# microcontroller.net
KiCad netlist of a schematic drawn in Altium Designer
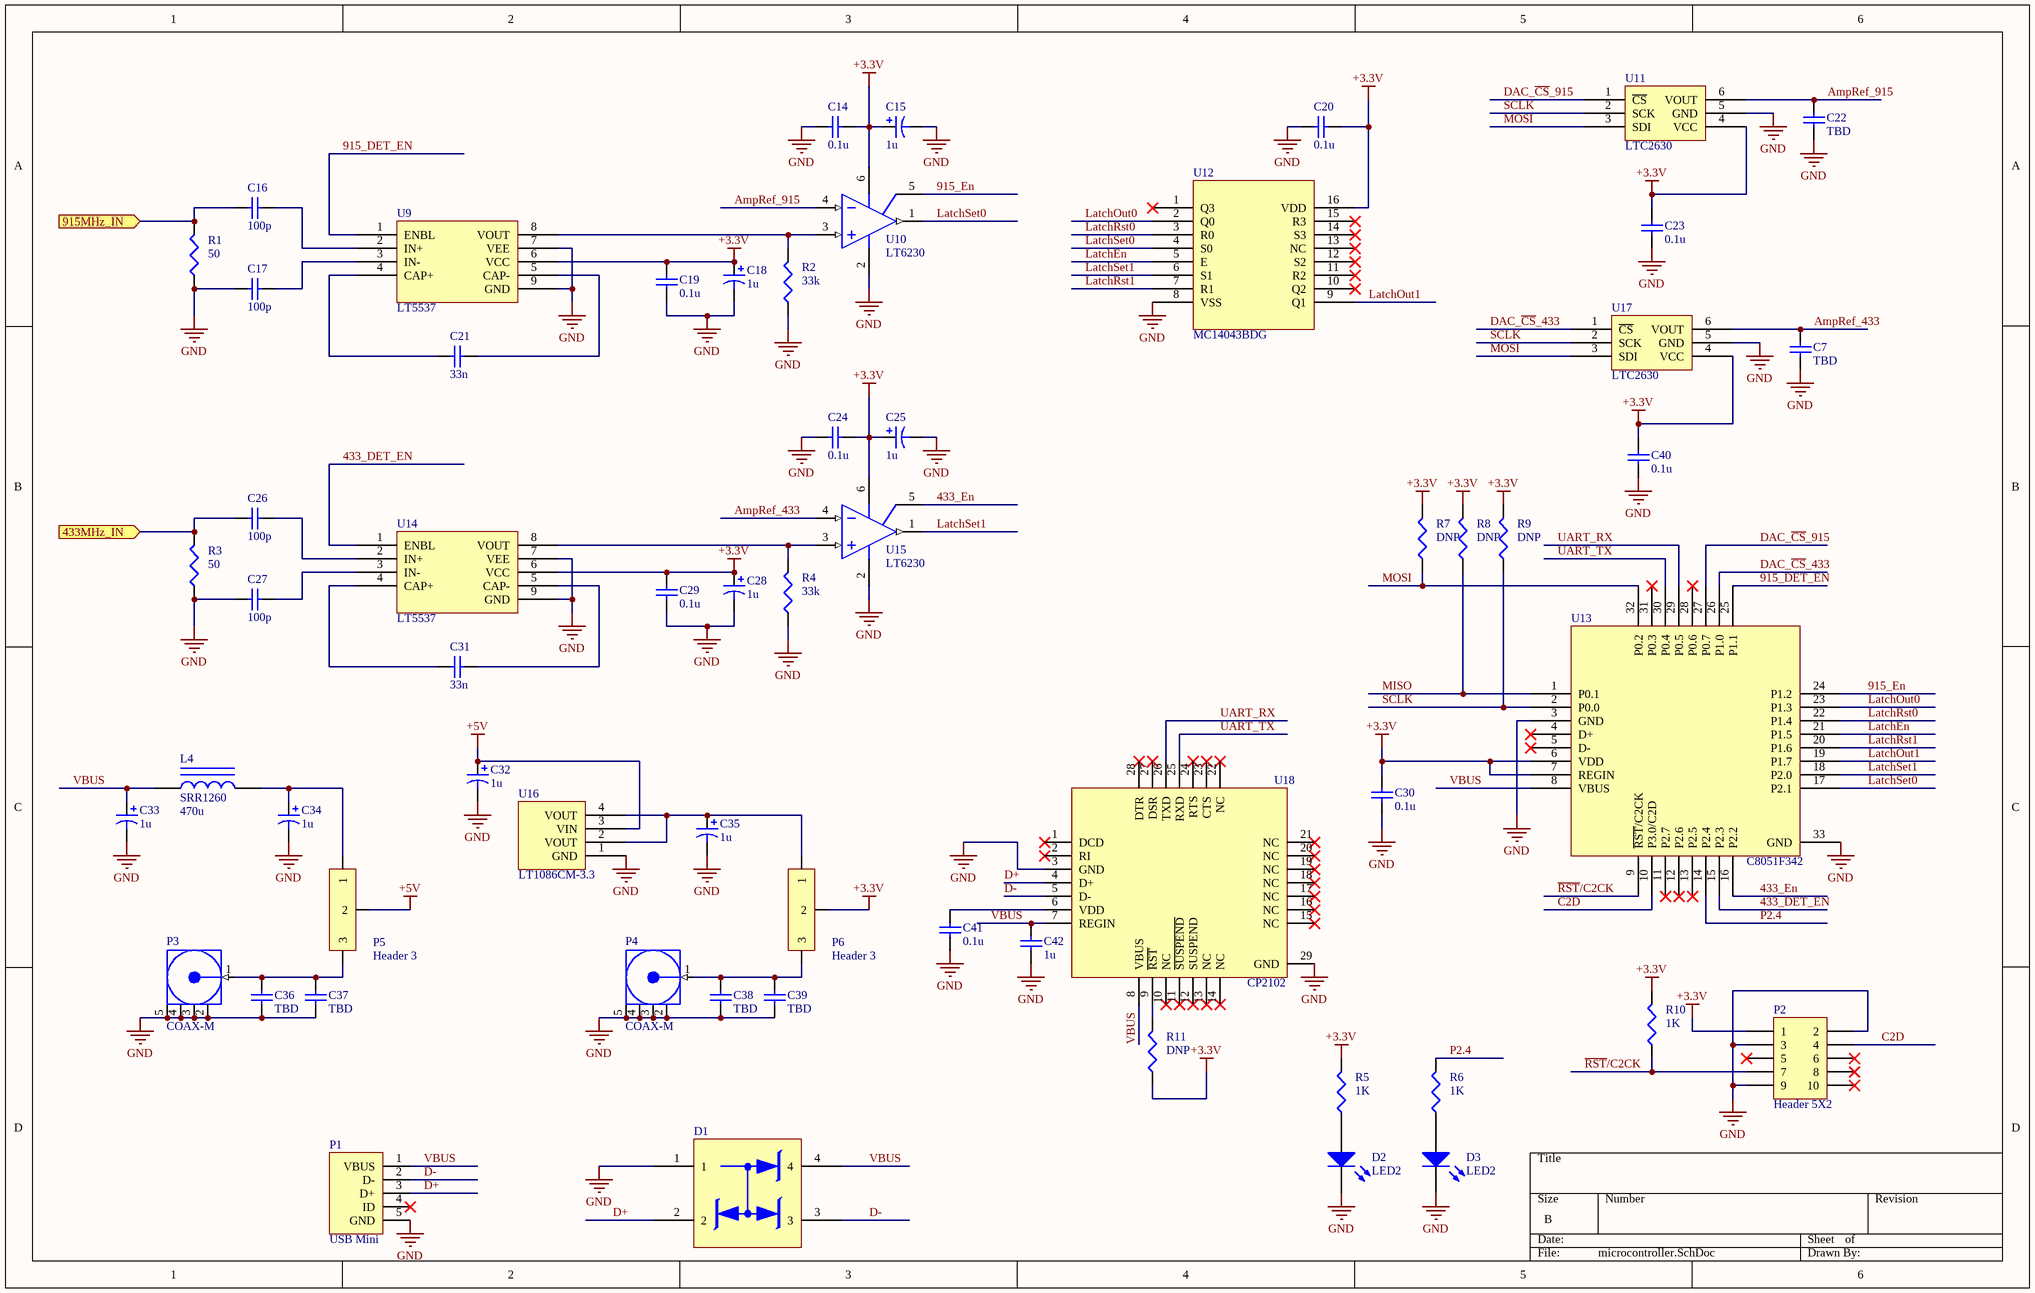
[diagram p0: microcontroller.SchDoc]

(export (version "E")
  (design (tool "Eeschema 10.0.6"))
  (components
    (comp (ref "C7")
      (value "TBD")
      (footprint "CAPC1608M")
      (description "Capacitor (Semiconductor SIM Model)")
      (fields (field (name "Comment") "Cap Semi") (field (name "PUBLISHER") "Altium Limited"))
      (libsource (lib "Miscellaneous Devices") (part "Cap Semi"))
    )
    (comp (ref "C14")
      (value "0.1u")
      (footprint "CAPC1608M")
      (description "Capacitor (Semiconductor SIM Model)")
      (fields (field (name "Comment") "Cap Semi") (field (name "PUBLISHER") "Altium Limited"))
      (libsource (lib "Miscellaneous Devices") (part "Cap Semi"))
    )
    (comp (ref "C15")
      (value "1u")
      (footprint "B")
      (description "Polarized Capacitor (Surface Mount)")
      (fields (field (name "Comment") "Cap Pol3") (field (name "PUBLISHER") "Altium Limited"))
      (libsource (lib "Miscellaneous Devices") (part "Cap Pol3"))
    )
    (comp (ref "C16")
      (value "100p")
      (footprint "CAPC1005L")
      (description "Capacitor (Semiconductor SIM Model)")
      (fields (field (name "Comment") "Cap Semi") (field (name "PUBLISHER") "Altium Limited"))
      (libsource (lib "Miscellaneous Devices") (part "Cap Semi"))
    )
    (comp (ref "C17")
      (value "100p")
      (footprint "CAPC1005L")
      (description "Capacitor (Semiconductor SIM Model)")
      (fields (field (name "Comment") "Cap Semi") (field (name "PUBLISHER") "Altium Limited"))
      (libsource (lib "Miscellaneous Devices") (part "Cap Semi"))
    )
    (comp (ref "C18")
      (value "1u")
      (footprint "B")
      (description "Polarized Capacitor (Surface Mount)")
      (fields (field (name "Comment") "Cap Pol3") (field (name "PUBLISHER") "Altium Limited"))
      (libsource (lib "Miscellaneous Devices") (part "Cap Pol3"))
    )
    (comp (ref "C19")
      (value "0.1u")
      (footprint "CAPC1608M")
      (description "Capacitor (Semiconductor SIM Model)")
      (fields (field (name "Comment") "Cap Semi") (field (name "PUBLISHER") "Altium Limited"))
      (libsource (lib "Miscellaneous Devices") (part "Cap Semi"))
    )
    (comp (ref "C20")
      (value "0.1u")
      (footprint "CAPC1608M")
      (description "Capacitor (Semiconductor SIM Model)")
      (fields (field (name "Comment") "Cap Semi") (field (name "PUBLISHER") "Altium Limited"))
      (libsource (lib "Miscellaneous Devices") (part "Cap Semi"))
    )
    (comp (ref "C21")
      (value "33n")
      (footprint "CAPC1005L")
      (description "Capacitor (Semiconductor SIM Model)")
      (fields (field (name "Comment") "Cap Semi") (field (name "PUBLISHER") "Altium Limited"))
      (libsource (lib "Miscellaneous Devices") (part "Cap Semi"))
    )
    (comp (ref "C22")
      (value "TBD")
      (footprint "CAPC1608M")
      (description "Capacitor (Semiconductor SIM Model)")
      (fields (field (name "Comment") "Cap Semi") (field (name "PUBLISHER") "Altium Limited"))
      (libsource (lib "Miscellaneous Devices") (part "Cap Semi"))
    )
    (comp (ref "C23")
      (value "0.1u")
      (footprint "CAPC1608M")
      (description "Capacitor (Semiconductor SIM Model)")
      (fields (field (name "Comment") "Cap Semi") (field (name "PUBLISHER") "Altium Limited"))
      (libsource (lib "Miscellaneous Devices") (part "Cap Semi"))
    )
    (comp (ref "C24")
      (value "0.1u")
      (footprint "CAPC1608M")
      (description "Capacitor (Semiconductor SIM Model)")
      (fields (field (name "Comment") "Cap Semi") (field (name "PUBLISHER") "Altium Limited"))
      (libsource (lib "Miscellaneous Devices") (part "Cap Semi"))
    )
    (comp (ref "C25")
      (value "1u")
      (footprint "B")
      (description "Polarized Capacitor (Surface Mount)")
      (fields (field (name "Comment") "Cap Pol3") (field (name "PUBLISHER") "Altium Limited"))
      (libsource (lib "Miscellaneous Devices") (part "Cap Pol3"))
    )
    (comp (ref "C26")
      (value "100p")
      (footprint "CAPC1005L")
      (description "Capacitor (Semiconductor SIM Model)")
      (fields (field (name "Comment") "Cap Semi") (field (name "PUBLISHER") "Altium Limited"))
      (libsource (lib "Miscellaneous Devices") (part "Cap Semi"))
    )
    (comp (ref "C27")
      (value "100p")
      (footprint "CAPC1005L")
      (description "Capacitor (Semiconductor SIM Model)")
      (fields (field (name "Comment") "Cap Semi") (field (name "PUBLISHER") "Altium Limited"))
      (libsource (lib "Miscellaneous Devices") (part "Cap Semi"))
    )
    (comp (ref "C28")
      (value "1u")
      (footprint "B")
      (description "Polarized Capacitor (Surface Mount)")
      (fields (field (name "Comment") "Cap Pol3") (field (name "PUBLISHER") "Altium Limited"))
      (libsource (lib "Miscellaneous Devices") (part "Cap Pol3"))
    )
    (comp (ref "C29")
      (value "0.1u")
      (footprint "CAPC1608M")
      (description "Capacitor (Semiconductor SIM Model)")
      (fields (field (name "Comment") "Cap Semi") (field (name "PUBLISHER") "Altium Limited"))
      (libsource (lib "Miscellaneous Devices") (part "Cap Semi"))
    )
    (comp (ref "C30")
      (value "0.1u")
      (footprint "CAPC1608M")
      (description "Capacitor (Semiconductor SIM Model)")
      (fields (field (name "Comment") "Cap Semi") (field (name "PUBLISHER") "Altium Limited"))
      (libsource (lib "Miscellaneous Devices") (part "Cap Semi"))
    )
    (comp (ref "C31")
      (value "33n")
      (footprint "CAPC1005L")
      (description "Capacitor (Semiconductor SIM Model)")
      (fields (field (name "Comment") "Cap Semi") (field (name "PUBLISHER") "Altium Limited"))
      (libsource (lib "Miscellaneous Devices") (part "Cap Semi"))
    )
    (comp (ref "C32")
      (value "1u")
      (footprint "B")
      (description "Polarized Capacitor (Surface Mount)")
      (fields (field (name "Comment") "Cap Pol3") (field (name "PUBLISHER") "Altium Limited"))
      (libsource (lib "Miscellaneous Devices") (part "Cap Pol3"))
    )
    (comp (ref "C33")
      (value "1u")
      (footprint "B")
      (description "Polarized Capacitor (Surface Mount)")
      (fields (field (name "Comment") "Cap Pol3") (field (name "PUBLISHER") "Altium Limited"))
      (libsource (lib "Miscellaneous Devices") (part "Cap Pol3"))
    )
    (comp (ref "C34")
      (value "1u")
      (footprint "B")
      (description "Polarized Capacitor (Surface Mount)")
      (fields (field (name "Comment") "Cap Pol3") (field (name "PUBLISHER") "Altium Limited"))
      (libsource (lib "Miscellaneous Devices") (part "Cap Pol3"))
    )
    (comp (ref "C35")
      (value "1u")
      (footprint "B")
      (description "Polarized Capacitor (Surface Mount)")
      (fields (field (name "Comment") "Cap Pol3") (field (name "PUBLISHER") "Altium Limited"))
      (libsource (lib "Miscellaneous Devices") (part "Cap Pol3"))
    )
    (comp (ref "C36")
      (value "TBD")
      (footprint "CAPC1608M")
      (description "Capacitor (Semiconductor SIM Model)")
      (fields (field (name "Comment") "Cap Semi") (field (name "PUBLISHER") "Altium Limited"))
      (libsource (lib "Miscellaneous Devices") (part "Cap Semi"))
    )
    (comp (ref "C37")
      (value "TBD")
      (footprint "CAPC1608M")
      (description "Capacitor (Semiconductor SIM Model)")
      (fields (field (name "Comment") "Cap Semi") (field (name "PUBLISHER") "Altium Limited"))
      (libsource (lib "Miscellaneous Devices") (part "Cap Semi"))
    )
    (comp (ref "C38")
      (value "TBD")
      (footprint "CAPC1608M")
      (description "Capacitor (Semiconductor SIM Model)")
      (fields (field (name "Comment") "Cap Semi") (field (name "PUBLISHER") "Altium Limited"))
      (libsource (lib "Miscellaneous Devices") (part "Cap Semi"))
    )
    (comp (ref "C39")
      (value "TBD")
      (footprint "CAPC1608M")
      (description "Capacitor (Semiconductor SIM Model)")
      (fields (field (name "Comment") "Cap Semi") (field (name "PUBLISHER") "Altium Limited"))
      (libsource (lib "Miscellaneous Devices") (part "Cap Semi"))
    )
    (comp (ref "C40")
      (value "0.1u")
      (footprint "CAPC1608M")
      (description "Capacitor (Semiconductor SIM Model)")
      (fields (field (name "Comment") "Cap Semi") (field (name "PUBLISHER") "Altium Limited"))
      (libsource (lib "Miscellaneous Devices") (part "Cap Semi"))
    )
    (comp (ref "C41")
      (value "0.1u")
      (footprint "CAPC1608M")
      (description "Capacitor (Semiconductor SIM Model)")
      (fields (field (name "Comment") "Cap Semi") (field (name "PUBLISHER") "Altium Limited"))
      (libsource (lib "Miscellaneous Devices") (part "Cap Semi"))
    )
    (comp (ref "C42")
      (value "1u")
      (footprint "CAPC1608M")
      (description "Capacitor (Semiconductor SIM Model)")
      (fields (field (name "Comment") "Cap Semi") (field (name "PUBLISHER") "Altium Limited"))
      (libsource (lib "Miscellaneous Devices") (part "Cap Semi"))
    )
    (comp (ref "D1")
      (value "SP0503BAHT")
      (footprint "SOT190P230X110-4M")
      (description "Littelfuse Inc - TVS AVAL DIODE ARRAY 3 CH SOT143")
      (fields (field (name "MANUFACTURER'S PART NO.") "SP0503BAHTG"))
      (libsource (lib "umich_schematic") (part "SP0503BAHT"))
    )
    (comp (ref "D2")
      (value "LED2")
      (footprint "3.2X1.6X1.1")
      (description "Typical RED, GREEN, YELLOW, AMBER GaAs LED")
      (fields (field (name "PUBLISHER") "Altium Limited"))
      (libsource (lib "Miscellaneous Devices") (part "LED2"))
    )
    (comp (ref "D3")
      (value "LED2")
      (footprint "3.2X1.6X1.1")
      (description "Typical RED, GREEN, YELLOW, AMBER GaAs LED")
      (fields (field (name "PUBLISHER") "Altium Limited"))
      (libsource (lib "Miscellaneous Devices") (part "LED2"))
    )
    (comp (ref "L4")
      (value "SRR1260")
      (footprint "SRR1260")
      (description "Magnetic-Core Inductor")
      (fields
        (field (name "ALTIUM_VALUE") "470u")
        (field (name "MANUFACTURER'S PART NO.") "SRR1260-471K")
        (field (name "PUBLISHER") "Altium Limited")
      )
      (libsource (lib "Miscellaneous Devices") (part "Inductor Iron"))
    )
    (comp (ref "P1")
      (value "USB Mini")
      (footprint "Hirose - ZX62-B-5PA(11)")
      (description "Hirose Electric Co Ltd - CONN RCPT MICRO USB B SMD R/A")
      (fields (field (name "MANUFACTURER'S PART NO.") "ZX62-B-5PA(11)"))
      (libsource (lib "umich_schematic") (part "USB Mini"))
    )
    (comp (ref "P2")
      (value "Header 5X2")
      (footprint "HDR2X5")
      (description "Header, 5-Pin, Dual row")
      (fields (field (name "PUBLISHER") "Altium Limited"))
      (libsource (lib "Miscellaneous Connectors") (part "Header 5X2"))
    )
    (comp (ref "P3")
      (value "COAX-M")
      (footprint "SMA Connector")
      (description "RF Coaxial PCB Connector, MMCX; Thru-Hole, Vertical Mount Plug,  50 Ohm Impedance")
      (fields (field (name "PUBLISHER") "Altium Limited"))
      (libsource (lib "Miscellaneous Connectors") (part "COAX-M"))
    )
    (comp (ref "P4")
      (value "COAX-M")
      (footprint "SMA Connector")
      (description "RF Coaxial PCB Connector, MMCX; Thru-Hole, Vertical Mount Plug,  50 Ohm Impedance")
      (fields (field (name "PUBLISHER") "Altium Limited"))
      (libsource (lib "Miscellaneous Connectors") (part "COAX-M"))
    )
    (comp (ref "P5")
      (value "Header 3")
      (footprint "HDR1X3")
      (description "3-pin, IDC Jumper")
      (fields (field (name "PUBLISHER") "Altium Limited"))
      (libsource (lib "umich_schematic") (part "Header 3"))
    )
    (comp (ref "P6")
      (value "Header 3")
      (footprint "HDR1X3")
      (description "3-pin, IDC Jumper")
      (fields (field (name "PUBLISHER") "Altium Limited"))
      (libsource (lib "umich_schematic") (part "Header 3"))
    )
    (comp (ref "R1")
      (value "50")
      (footprint "RESC1005L")
      (description "Resistor")
      (fields (field (name "Comment") "Res3") (field (name "PUBLISHER") "Altium Limited"))
      (libsource (lib "Miscellaneous Devices") (part "Res3"))
    )
    (comp (ref "R2")
      (value "33k")
      (footprint "RESC1608M")
      (description "Resistor")
      (fields (field (name "Comment") "Res3") (field (name "PUBLISHER") "Altium Limited"))
      (libsource (lib "Miscellaneous Devices") (part "Res3"))
    )
    (comp (ref "R3")
      (value "50")
      (footprint "RESC1005L")
      (description "Resistor")
      (fields (field (name "Comment") "Res3") (field (name "PUBLISHER") "Altium Limited"))
      (libsource (lib "Miscellaneous Devices") (part "Res3"))
    )
    (comp (ref "R4")
      (value "33k")
      (footprint "RESC1608M")
      (description "Resistor")
      (fields (field (name "Comment") "Res3") (field (name "PUBLISHER") "Altium Limited"))
      (libsource (lib "Miscellaneous Devices") (part "Res3"))
    )
    (comp (ref "R5")
      (value "1K")
      (footprint "RESC1608M")
      (description "Resistor")
      (fields (field (name "Comment") "Res3") (field (name "PUBLISHER") "Altium Limited"))
      (libsource (lib "Miscellaneous Devices") (part "Res3"))
    )
    (comp (ref "R6")
      (value "1K")
      (footprint "RESC1608M")
      (description "Resistor")
      (fields (field (name "Comment") "Res3") (field (name "PUBLISHER") "Altium Limited"))
      (libsource (lib "Miscellaneous Devices") (part "Res3"))
    )
    (comp (ref "R7")
      (value "DNP")
      (footprint "RESC1608M")
      (description "Resistor")
      (fields (field (name "Comment") "Res3") (field (name "PUBLISHER") "Altium Limited"))
      (libsource (lib "Miscellaneous Devices") (part "Res3"))
    )
    (comp (ref "R8")
      (value "DNP")
      (footprint "RESC1608M")
      (description "Resistor")
      (fields (field (name "Comment") "Res3") (field (name "PUBLISHER") "Altium Limited"))
      (libsource (lib "Miscellaneous Devices") (part "Res3"))
    )
    (comp (ref "R9")
      (value "DNP")
      (footprint "RESC1608M")
      (description "Resistor")
      (fields (field (name "Comment") "Res3") (field (name "PUBLISHER") "Altium Limited"))
      (libsource (lib "Miscellaneous Devices") (part "Res3"))
    )
    (comp (ref "R10")
      (value "1K")
      (footprint "RESC1608M")
      (description "Resistor")
      (fields (field (name "Comment") "Res3") (field (name "PUBLISHER") "Altium Limited"))
      (libsource (lib "Miscellaneous Devices") (part "Res3"))
    )
    (comp (ref "R11")
      (value "DNP")
      (footprint "RESC1608M")
      (description "Resistor")
      (fields (field (name "Comment") "Res3") (field (name "PUBLISHER") "Altium Limited"))
      (libsource (lib "Miscellaneous Devices") (part "Res3"))
    )
    (comp (ref "U9")
      (value "LT5537")
      (footprint "DDB Package")
      (description "Linear Technology - IC RF/IF LOG DETECTOR 8-DFN")
      (fields (field (name "MANUFACTURER'S PART NO.") "LT5537EDDB#TRMPBF"))
      (libsource (lib "umich_schematic") (part "LT5537"))
    )
    (comp (ref "U10")
      (value "LT6230")
      (footprint "SOT100P275-6M")
      (description "Linear Technology - IC OP AMP 3.4MA 215MHZ SOT23-6")
      (fields (field (name "MANUFACTURER'S PART NO.") "LT6230CS6#TRMPBF"))
      (libsource (lib "umich_schematic") (part "LT6230"))
    )
    (comp (ref "U11")
      (value "LTC2630")
      (footprint "SOT100P275-6M")
      (description "Linear Technology - IC DAC 12BIT R-R SC70-6")
      (fields (field (name "MANUFACTURER'S PART NO.") "LTC2630ISC6-LZ12#TRMPBF"))
      (libsource (lib "umich_schematic") (part "LTC2630"))
    )
    (comp (ref "U12")
      (value "MC14043BDG")
      (footprint "SOIC127P602-16BM")
      (description "ON Semiconductor - IC LATCH R-S QUAD NOR 16SOIC")
      (libsource (lib "umich_schematic") (part "MC14043BDG"))
    )
    (comp (ref "U13")
      (value "C8051F342")
      (footprint "QFN50P500X500-32VBM")
      (description "Silicon Laboratories Inc - IC 8051 MCU 64K FLASH MEM 32-QFN")
      (fields (field (name "MANUFACTURER'S PART NO.") "C8051F342-GM"))
      (libsource (lib "umich_schematic") (part "C8051F342"))
    )
    (comp (ref "U14")
      (value "LT5537")
      (footprint "DDB Package")
      (description "Linear Technology - IC RF/IF LOG DETECTOR 8-DFN")
      (fields (field (name "MANUFACTURER'S PART NO.") "LT5537EDDB#TRMPBF"))
      (libsource (lib "umich_schematic") (part "LT5537"))
    )
    (comp (ref "U15")
      (value "LT6230")
      (footprint "SOT100P275-6M")
      (description "Linear Technology - IC OP AMP 3.4MA 215MHZ SOT23-6")
      (fields (field (name "MANUFACTURER'S PART NO.") "LT6230CS6#TRMPBF"))
      (libsource (lib "umich_schematic") (part "LT6230"))
    )
    (comp (ref "U16")
      (value "LT1086CM-3.3")
      (footprint "TO254P1420-4AM")
      (description "Linear Technology - IC REG LDO 3.3V 3DD")
      (fields (field (name "MANUFACTURER'S PART NO.") "LT1086CM-3.3#PBF"))
      (libsource (lib "umich_schematic") (part "LT1086CM-3.3"))
    )
    (comp (ref "U17")
      (value "LTC2630")
      (footprint "SOT100P275-6M")
      (description "Linear Technology - IC DAC 12BIT R-R SC70-6")
      (fields (field (name "MANUFACTURER'S PART NO.") "LTC2630ISC6-LZ12#TRMPBF"))
      (libsource (lib "umich_schematic") (part "LTC2630"))
    )
    (comp (ref "U18")
      (value "CP2102")
      (footprint "QFN50P500X500-28V1L")
      (description "IC USB-TO-UART BRIDGE 28VQFN")
      (libsource (lib "umich_schematic") (part "CP2102"))
    )
  )
  (nets
    (net (code "1") (name "+3.3V") (class "Default")
      (node (ref "C14") (pin "2") (pinfunction "2_2") (pintype "passive"))
      (node (ref "C15") (pin "1") (pinfunction "1_1") (pintype "passive"))
      (node (ref "C18") (pin "1") (pinfunction "1_1") (pintype "passive"))
      (node (ref "C19") (pin "1") (pinfunction "1_1") (pintype "passive"))
      (node (ref "C20") (pin "2") (pinfunction "2_2") (pintype "passive"))
      (node (ref "C23") (pin "2") (pinfunction "2_2") (pintype "passive"))
      (node (ref "C24") (pin "2") (pinfunction "2_2") (pintype "passive"))
      (node (ref "C25") (pin "1") (pinfunction "1_1") (pintype "passive"))
      (node (ref "C28") (pin "1") (pinfunction "1_1") (pintype "passive"))
      (node (ref "C29") (pin "1") (pinfunction "1_1") (pintype "passive"))
      (node (ref "C30") (pin "2") (pinfunction "2_2") (pintype "passive"))
      (node (ref "C40") (pin "2") (pinfunction "2_2") (pintype "passive"))
      (node (ref "P2") (pin "1") (pinfunction "1_1") (pintype "passive"))
      (node (ref "P6") (pin "2") (pinfunction "2_2") (pintype "passive"))
      (node (ref "R10") (pin "2") (pinfunction "2_2") (pintype "passive"))
      (node (ref "R11") (pin "1") (pinfunction "1_1") (pintype "passive"))
      (node (ref "R5") (pin "2") (pinfunction "2_2") (pintype "passive"))
      (node (ref "R7") (pin "2") (pinfunction "2_2") (pintype "passive"))
      (node (ref "R8") (pin "2") (pinfunction "2_2") (pintype "passive"))
      (node (ref "R9") (pin "2") (pinfunction "2_2") (pintype "passive"))
      (node (ref "U10") (pin "6") (pinfunction "V+_6") (pintype "power_in"))
      (node (ref "U11") (pin "4") (pinfunction "VCC_4") (pintype "passive"))
      (node (ref "U12") (pin "16") (pinfunction "VDD_16") (pintype "passive"))
      (node (ref "U13") (pin "6") (pinfunction "VDD_6") (pintype "passive"))
      (node (ref "U13") (pin "7") (pinfunction "REGIN_7") (pintype "passive"))
      (node (ref "U14") (pin "6") (pinfunction "VCC_6") (pintype "passive"))
      (node (ref "U15") (pin "6") (pinfunction "V+_6") (pintype "power_in"))
      (node (ref "U17") (pin "4") (pinfunction "VCC_4") (pintype "passive"))
      (node (ref "U9") (pin "6") (pinfunction "VCC_6") (pintype "passive"))
    )
    (net (code "2") (name "+5V") (class "Default")
      (node (ref "C32") (pin "1") (pinfunction "1_1") (pintype "passive"))
      (node (ref "P5") (pin "2") (pinfunction "2_2") (pintype "passive"))
      (node (ref "U16") (pin "3") (pinfunction "VIN_3") (pintype "passive"))
    )
    (net (code "3") (name "/433MHz_IN") (class "Default")
      (node (ref "C26") (pin "2") (pinfunction "2_2") (pintype "passive"))
      (node (ref "R3") (pin "2") (pinfunction "2_2") (pintype "passive"))
    )
    (net (code "4") (name "/433_DET_EN") (class "Default")
      (node (ref "U13") (pin "15") (pinfunction "P2.3_15") (pintype "passive"))
      (node (ref "U14") (pin "1") (pinfunction "ENBL_1") (pintype "passive"))
    )
    (net (code "5") (name "/433_En") (class "Default")
      (node (ref "U13") (pin "16") (pinfunction "P2.2_16") (pintype "passive"))
      (node (ref "U15") (pin "5") (pinfunction "~{ENABLE}_5") (pintype "passive"))
    )
    (net (code "6") (name "/915MHz_IN") (class "Default")
      (node (ref "C16") (pin "2") (pinfunction "2_2") (pintype "passive"))
      (node (ref "R1") (pin "2") (pinfunction "2_2") (pintype "passive"))
    )
    (net (code "7") (name "/915_DET_EN") (class "Default")
      (node (ref "U13") (pin "25") (pinfunction "P1.1_25") (pintype "passive"))
      (node (ref "U9") (pin "1") (pinfunction "ENBL_1") (pintype "passive"))
    )
    (net (code "8") (name "/915_En") (class "Default")
      (node (ref "U10") (pin "5") (pinfunction "~{ENABLE}_5") (pintype "passive"))
      (node (ref "U13") (pin "24") (pinfunction "P1.2_24") (pintype "passive"))
    )
    (net (code "9") (name "/AmpRef_433") (class "Default")
      (node (ref "C7") (pin "2") (pinfunction "2_2") (pintype "passive"))
      (node (ref "U15") (pin "4") (pinfunction "-IN_4") (pintype "input"))
      (node (ref "U17") (pin "6") (pinfunction "VOUT_6") (pintype "passive"))
    )
    (net (code "10") (name "/AmpRef_915") (class "Default")
      (node (ref "C22") (pin "2") (pinfunction "2_2") (pintype "passive"))
      (node (ref "U10") (pin "4") (pinfunction "-IN_4") (pintype "input"))
      (node (ref "U11") (pin "6") (pinfunction "VOUT_6") (pintype "passive"))
    )
    (net (code "11") (name "/C2D") (class "Default")
      (node (ref "P2") (pin "4") (pinfunction "4_4") (pintype "passive"))
      (node (ref "U13") (pin "10") (pinfunction "P3.0/C2D_10") (pintype "passive"))
    )
    (net (code "12") (name "/D+") (class "Default")
      (node (ref "D1") (pin "2") (pinfunction "2_2") (pintype "passive"))
      (node (ref "P1") (pin "3") (pinfunction "D+_3") (pintype "passive"))
      (node (ref "U18") (pin "4") (pinfunction "D+_4") (pintype "passive"))
    )
    (net (code "13") (name "/D-") (class "Default")
      (node (ref "D1") (pin "3") (pinfunction "3_3") (pintype "passive"))
      (node (ref "P1") (pin "2") (pinfunction "D-_2") (pintype "passive"))
      (node (ref "U18") (pin "5") (pinfunction "D-_5") (pintype "passive"))
    )
    (net (code "14") (name "/DAC_~{CS}_433") (class "Default")
      (node (ref "U13") (pin "26") (pinfunction "P1.0_26") (pintype "passive"))
      (node (ref "U17") (pin "1") (pinfunction "~{CS}_1") (pintype "passive"))
    )
    (net (code "15") (name "/DAC_~{CS}_915") (class "Default")
      (node (ref "U11") (pin "1") (pinfunction "~{CS}_1") (pintype "passive"))
      (node (ref "U13") (pin "27") (pinfunction "P0.7_27") (pintype "passive"))
    )
    (net (code "16") (name "/LatchEn") (class "Default")
      (node (ref "U12") (pin "5") (pinfunction "E_5") (pintype "passive"))
      (node (ref "U13") (pin "21") (pinfunction "P1.5_21") (pintype "passive"))
    )
    (net (code "17") (name "/LatchOut0") (class "Default")
      (node (ref "U12") (pin "2") (pinfunction "Q0_2") (pintype "passive"))
      (node (ref "U13") (pin "23") (pinfunction "P1.3_23") (pintype "passive"))
    )
    (net (code "18") (name "/LatchOut1") (class "Default")
      (node (ref "U12") (pin "9") (pinfunction "Q1_9") (pintype "passive"))
      (node (ref "U13") (pin "19") (pinfunction "P1.7_19") (pintype "passive"))
    )
    (net (code "19") (name "/LatchRst0") (class "Default")
      (node (ref "U12") (pin "3") (pinfunction "R0_3") (pintype "passive"))
      (node (ref "U13") (pin "22") (pinfunction "P1.4_22") (pintype "passive"))
    )
    (net (code "20") (name "/LatchRst1") (class "Default")
      (node (ref "U12") (pin "7") (pinfunction "R1_7") (pintype "passive"))
      (node (ref "U13") (pin "20") (pinfunction "P1.6_20") (pintype "passive"))
    )
    (net (code "21") (name "/LatchSet0") (class "Default")
      (node (ref "U10") (pin "1") (pinfunction "OUT_1") (pintype "output"))
      (node (ref "U12") (pin "4") (pinfunction "S0_4") (pintype "passive"))
      (node (ref "U13") (pin "17") (pinfunction "P2.1_17") (pintype "passive"))
    )
    (net (code "22") (name "/LatchSet1") (class "Default")
      (node (ref "U12") (pin "6") (pinfunction "S1_6") (pintype "passive"))
      (node (ref "U13") (pin "18") (pinfunction "P2.0_18") (pintype "passive"))
      (node (ref "U15") (pin "1") (pinfunction "OUT_1") (pintype "output"))
    )
    (net (code "23") (name "/MISO") (class "Default")
      (node (ref "R8") (pin "1") (pinfunction "1_1") (pintype "passive"))
      (node (ref "U13") (pin "1") (pinfunction "P0.1_1") (pintype "passive"))
    )
    (net (code "24") (name "/MOSI") (class "Default")
      (node (ref "R7") (pin "1") (pinfunction "1_1") (pintype "passive"))
      (node (ref "U11") (pin "3") (pinfunction "SDI_3") (pintype "passive"))
      (node (ref "U13") (pin "32") (pinfunction "P0.2_32") (pintype "passive"))
      (node (ref "U17") (pin "3") (pinfunction "SDI_3") (pintype "passive"))
    )
    (net (code "25") (name "/P2.4") (class "Default")
      (node (ref "R6") (pin "2") (pinfunction "2_2") (pintype "passive"))
      (node (ref "U13") (pin "14") (pinfunction "P2.4_14") (pintype "passive"))
    )
    (net (code "26") (name "/SCLK") (class "Default")
      (node (ref "R9") (pin "1") (pinfunction "1_1") (pintype "passive"))
      (node (ref "U11") (pin "2") (pinfunction "SCK_2") (pintype "passive"))
      (node (ref "U13") (pin "2") (pinfunction "P0.0_2") (pintype "passive"))
      (node (ref "U17") (pin "2") (pinfunction "SCK_2") (pintype "passive"))
    )
    (net (code "27") (name "/UART_RX") (class "Default")
      (node (ref "U13") (pin "29") (pinfunction "P0.5_29") (pintype "passive"))
      (node (ref "U18") (pin "26") (pinfunction "TXD_26") (pintype "passive"))
    )
    (net (code "28") (name "/UART_TX") (class "Default")
      (node (ref "U13") (pin "30") (pinfunction "P0.4_30") (pintype "passive"))
      (node (ref "U18") (pin "25") (pinfunction "RXD_25") (pintype "passive"))
    )
    (net (code "29") (name "/VBUS") (class "Default")
      (node (ref "C33") (pin "1") (pinfunction "1_1") (pintype "passive"))
      (node (ref "C42") (pin "2") (pinfunction "2_2") (pintype "passive"))
      (node (ref "D1") (pin "4") (pinfunction "4_4") (pintype "passive"))
      (node (ref "L4") (pin "1") (pinfunction "1_1") (pintype "passive"))
      (node (ref "P1") (pin "1") (pinfunction "VBUS_1") (pintype "passive"))
      (node (ref "U13") (pin "8") (pinfunction "VBUS_8") (pintype "passive"))
      (node (ref "U18") (pin "7") (pinfunction "REGIN_7") (pintype "passive"))
      (node (ref "U18") (pin "8") (pinfunction "VBUS_8") (pintype "passive"))
    )
    (net (code "30") (name "/~{RST}{slash}C2CK") (class "Default")
      (node (ref "P2") (pin "7") (pinfunction "7_7") (pintype "passive"))
      (node (ref "R10") (pin "1") (pinfunction "1_1") (pintype "passive"))
      (node (ref "U13") (pin "9") (pinfunction "~{RST}/C2CK_9") (pintype "passive"))
    )
    (net (code "31") (name "GND") (class "Default")
      (node (ref "C14") (pin "1") (pinfunction "1_1") (pintype "passive"))
      (node (ref "C15") (pin "2") (pinfunction "2_2") (pintype "passive"))
      (node (ref "C17") (pin "2") (pinfunction "2_2") (pintype "passive"))
      (node (ref "C18") (pin "2") (pinfunction "2_2") (pintype "passive"))
      (node (ref "C19") (pin "2") (pinfunction "2_2") (pintype "passive"))
      (node (ref "C20") (pin "1") (pinfunction "1_1") (pintype "passive"))
      (node (ref "C22") (pin "1") (pinfunction "1_1") (pintype "passive"))
      (node (ref "C23") (pin "1") (pinfunction "1_1") (pintype "passive"))
      (node (ref "C24") (pin "1") (pinfunction "1_1") (pintype "passive"))
      (node (ref "C25") (pin "2") (pinfunction "2_2") (pintype "passive"))
      (node (ref "C27") (pin "2") (pinfunction "2_2") (pintype "passive"))
      (node (ref "C28") (pin "2") (pinfunction "2_2") (pintype "passive"))
      (node (ref "C29") (pin "2") (pinfunction "2_2") (pintype "passive"))
      (node (ref "C30") (pin "1") (pinfunction "1_1") (pintype "passive"))
      (node (ref "C32") (pin "2") (pinfunction "2_2") (pintype "passive"))
      (node (ref "C33") (pin "2") (pinfunction "2_2") (pintype "passive"))
      (node (ref "C34") (pin "2") (pinfunction "2_2") (pintype "passive"))
      (node (ref "C35") (pin "2") (pinfunction "2_2") (pintype "passive"))
      (node (ref "C36") (pin "2") (pinfunction "2_2") (pintype "passive"))
      (node (ref "C37") (pin "2") (pinfunction "2_2") (pintype "passive"))
      (node (ref "C38") (pin "2") (pinfunction "2_2") (pintype "passive"))
      (node (ref "C39") (pin "2") (pinfunction "2_2") (pintype "passive"))
      (node (ref "C40") (pin "1") (pinfunction "1_1") (pintype "passive"))
      (node (ref "C41") (pin "1") (pinfunction "1_1") (pintype "passive"))
      (node (ref "C42") (pin "1") (pinfunction "1_1") (pintype "passive"))
      (node (ref "C7") (pin "1") (pinfunction "1_1") (pintype "passive"))
      (node (ref "D1") (pin "1") (pinfunction "1_1") (pintype "passive"))
      (node (ref "D2") (pin "2") (pinfunction "K_2") (pintype "passive"))
      (node (ref "D3") (pin "2") (pinfunction "K_2") (pintype "passive"))
      (node (ref "P1") (pin "5") (pinfunction "GND_5") (pintype "passive"))
      (node (ref "P2") (pin "2") (pinfunction "2_2") (pintype "passive"))
      (node (ref "P2") (pin "3") (pinfunction "3_3") (pintype "passive"))
      (node (ref "P2") (pin "9") (pinfunction "9_9") (pintype "passive"))
      (node (ref "P3") (pin "2") (pinfunction "GND_2") (pintype "power_in"))
      (node (ref "P3") (pin "3") (pinfunction "GND_3") (pintype "power_in"))
      (node (ref "P3") (pin "4") (pinfunction "GND_4") (pintype "power_in"))
      (node (ref "P3") (pin "5") (pinfunction "GND_5") (pintype "power_in"))
      (node (ref "P4") (pin "2") (pinfunction "GND_2") (pintype "power_in"))
      (node (ref "P4") (pin "3") (pinfunction "GND_3") (pintype "power_in"))
      (node (ref "P4") (pin "4") (pinfunction "GND_4") (pintype "power_in"))
      (node (ref "P4") (pin "5") (pinfunction "GND_5") (pintype "power_in"))
      (node (ref "R1") (pin "1") (pinfunction "1_1") (pintype "passive"))
      (node (ref "R2") (pin "1") (pinfunction "1_1") (pintype "passive"))
      (node (ref "R3") (pin "1") (pinfunction "1_1") (pintype "passive"))
      (node (ref "R4") (pin "1") (pinfunction "1_1") (pintype "passive"))
      (node (ref "U10") (pin "2") (pinfunction "V-_2") (pintype "power_in"))
      (node (ref "U11") (pin "5") (pinfunction "GND_5") (pintype "passive"))
      (node (ref "U12") (pin "8") (pinfunction "VSS_8") (pintype "passive"))
      (node (ref "U13") (pin "3") (pinfunction "GND_3") (pintype "passive"))
      (node (ref "U13") (pin "33") (pinfunction "GND_33") (pintype "passive"))
      (node (ref "U14") (pin "7") (pinfunction "VEE_7") (pintype "passive"))
      (node (ref "U14") (pin "9") (pinfunction "GND_9") (pintype "passive"))
      (node (ref "U15") (pin "2") (pinfunction "V-_2") (pintype "power_in"))
      (node (ref "U16") (pin "1") (pinfunction "GND_1") (pintype "passive"))
      (node (ref "U17") (pin "5") (pinfunction "GND_5") (pintype "passive"))
      (node (ref "U18") (pin "29") (pinfunction "GND_29") (pintype "passive"))
      (node (ref "U18") (pin "3") (pinfunction "GND_3") (pintype "passive"))
      (node (ref "U9") (pin "7") (pinfunction "VEE_7") (pintype "passive"))
      (node (ref "U9") (pin "9") (pinfunction "GND_9") (pintype "passive"))
    )
    (net (code "32") (name "Net-(C34-Pad1)") (class "Default")
      (node (ref "C34") (pin "1") (pinfunction "1_1") (pintype "passive"))
      (node (ref "L4") (pin "2") (pinfunction "2_2") (pintype "passive"))
      (node (ref "P5") (pin "1") (pinfunction "1_1") (pintype "passive"))
    )
    (net (code "33") (name "Net-(C35-Pad1)") (class "Default")
      (node (ref "C35") (pin "1") (pinfunction "1_1") (pintype "passive"))
      (node (ref "P6") (pin "1") (pinfunction "1_1") (pintype "passive"))
      (node (ref "U16") (pin "2") (pinfunction "VOUT_2") (pintype "passive"))
      (node (ref "U16") (pin "4") (pinfunction "VOUT_4") (pintype "passive"))
    )
    (net (code "34") (name "Net-(D2-A)") (class "Default")
      (node (ref "D2") (pin "1") (pinfunction "A_1") (pintype "passive"))
      (node (ref "R5") (pin "1") (pinfunction "1_1") (pintype "passive"))
    )
    (net (code "35") (name "Net-(D3-A)") (class "Default")
      (node (ref "D3") (pin "1") (pinfunction "A_1") (pintype "passive"))
      (node (ref "R6") (pin "1") (pinfunction "1_1") (pintype "passive"))
    )
    (net (code "36") (name "Net-(P3-Signal)") (class "Default")
      (node (ref "C36") (pin "1") (pinfunction "1_1") (pintype "passive"))
      (node (ref "C37") (pin "1") (pinfunction "1_1") (pintype "passive"))
      (node (ref "P3") (pin "1") (pinfunction "Signal_1") (pintype "input"))
      (node (ref "P5") (pin "3") (pinfunction "3_3") (pintype "passive"))
    )
    (net (code "37") (name "Net-(P4-Signal)") (class "Default")
      (node (ref "C38") (pin "1") (pinfunction "1_1") (pintype "passive"))
      (node (ref "C39") (pin "1") (pinfunction "1_1") (pintype "passive"))
      (node (ref "P4") (pin "1") (pinfunction "Signal_1") (pintype "input"))
      (node (ref "P6") (pin "3") (pinfunction "3_3") (pintype "passive"))
    )
    (net (code "38") (name "Net-(U9-CAP+)") (class "Default")
      (node (ref "C21") (pin "2") (pinfunction "2_2") (pintype "passive"))
      (node (ref "U9") (pin "4") (pinfunction "CAP+_4") (pintype "passive"))
    )
    (net (code "39") (name "Net-(U9-CAP-)") (class "Default")
      (node (ref "C21") (pin "1") (pinfunction "1_1") (pintype "passive"))
      (node (ref "U9") (pin "5") (pinfunction "CAP-_5") (pintype "passive"))
    )
    (net (code "40") (name "Net-(U9-IN+)") (class "Default")
      (node (ref "C16") (pin "1") (pinfunction "1_1") (pintype "passive"))
      (node (ref "U9") (pin "2") (pinfunction "IN+_2") (pintype "passive"))
    )
    (net (code "41") (name "Net-(U9-IN-)") (class "Default")
      (node (ref "C17") (pin "1") (pinfunction "1_1") (pintype "passive"))
      (node (ref "U9") (pin "3") (pinfunction "IN-_3") (pintype "passive"))
    )
    (net (code "42") (name "Net-(U10-+IN)") (class "Default")
      (node (ref "R2") (pin "2") (pinfunction "2_2") (pintype "passive"))
      (node (ref "U10") (pin "3") (pinfunction "+IN_3") (pintype "input"))
      (node (ref "U9") (pin "8") (pinfunction "VOUT_8") (pintype "passive"))
    )
    (net (code "43") (name "Net-(U14-CAP+)") (class "Default")
      (node (ref "C31") (pin "2") (pinfunction "2_2") (pintype "passive"))
      (node (ref "U14") (pin "4") (pinfunction "CAP+_4") (pintype "passive"))
    )
    (net (code "44") (name "Net-(U14-CAP-)") (class "Default")
      (node (ref "C31") (pin "1") (pinfunction "1_1") (pintype "passive"))
      (node (ref "U14") (pin "5") (pinfunction "CAP-_5") (pintype "passive"))
    )
    (net (code "45") (name "Net-(U14-IN+)") (class "Default")
      (node (ref "C26") (pin "1") (pinfunction "1_1") (pintype "passive"))
      (node (ref "U14") (pin "2") (pinfunction "IN+_2") (pintype "passive"))
    )
    (net (code "46") (name "Net-(U14-IN-)") (class "Default")
      (node (ref "C27") (pin "1") (pinfunction "1_1") (pintype "passive"))
      (node (ref "U14") (pin "3") (pinfunction "IN-_3") (pintype "passive"))
    )
    (net (code "47") (name "Net-(U14-VOUT)") (class "Default")
      (node (ref "R4") (pin "2") (pinfunction "2_2") (pintype "passive"))
      (node (ref "U14") (pin "8") (pinfunction "VOUT_8") (pintype "passive"))
      (node (ref "U15") (pin "3") (pinfunction "+IN_3") (pintype "input"))
    )
    (net (code "48") (name "Net-(U18-VDD)") (class "Default")
      (node (ref "C41") (pin "2") (pinfunction "2_2") (pintype "passive"))
      (node (ref "U18") (pin "6") (pinfunction "VDD_6") (pintype "passive"))
    )
    (net (code "49") (name "Net-(U18-~{RST})") (class "Default")
      (node (ref "R11") (pin "2") (pinfunction "2_2") (pintype "passive"))
      (node (ref "U18") (pin "9") (pinfunction "~{RST}_9") (pintype "passive"))
    )
    (net (code "50") (name "unconnected-(P1-ID-Pad4)") (class "Default")
      (node (ref "P1") (pin "4") (pinfunction "ID_4") (pintype "passive+no_connect"))
    )
    (net (code "51") (name "unconnected-(P2-Pad5)") (class "Default")
      (node (ref "P2") (pin "5") (pinfunction "5_5") (pintype "passive+no_connect"))
    )
    (net (code "52") (name "unconnected-(P2-Pad6)") (class "Default")
      (node (ref "P2") (pin "6") (pinfunction "6_6") (pintype "passive+no_connect"))
    )
    (net (code "53") (name "unconnected-(P2-Pad8)") (class "Default")
      (node (ref "P2") (pin "8") (pinfunction "8_8") (pintype "passive+no_connect"))
    )
    (net (code "54") (name "unconnected-(P2-Pad10)") (class "Default")
      (node (ref "P2") (pin "10") (pinfunction "10_10") (pintype "passive+no_connect"))
    )
    (net (code "55") (name "unconnected-(U12-NC-Pad13)") (class "Default")
      (node (ref "U12") (pin "13") (pinfunction "NC_13") (pintype "passive+no_connect"))
    )
    (net (code "56") (name "unconnected-(U12-Q2-Pad10)") (class "Default")
      (node (ref "U12") (pin "10") (pinfunction "Q2_10") (pintype "passive+no_connect"))
    )
    (net (code "57") (name "unconnected-(U12-Q3-Pad1)") (class "Default")
      (node (ref "U12") (pin "1") (pinfunction "Q3_1") (pintype "passive+no_connect"))
    )
    (net (code "58") (name "unconnected-(U12-R2-Pad11)") (class "Default")
      (node (ref "U12") (pin "11") (pinfunction "R2_11") (pintype "passive+no_connect"))
    )
    (net (code "59") (name "unconnected-(U12-R3-Pad15)") (class "Default")
      (node (ref "U12") (pin "15") (pinfunction "R3_15") (pintype "passive+no_connect"))
    )
    (net (code "60") (name "unconnected-(U12-S2-Pad12)") (class "Default")
      (node (ref "U12") (pin "12") (pinfunction "S2_12") (pintype "passive+no_connect"))
    )
    (net (code "61") (name "unconnected-(U12-S3-Pad14)") (class "Default")
      (node (ref "U12") (pin "14") (pinfunction "S3_14") (pintype "passive+no_connect"))
    )
    (net (code "62") (name "unconnected-(U13-D+-Pad4)") (class "Default")
      (node (ref "U13") (pin "4") (pinfunction "D+_4") (pintype "passive+no_connect"))
    )
    (net (code "63") (name "unconnected-(U13-D--Pad5)") (class "Default")
      (node (ref "U13") (pin "5") (pinfunction "D-_5") (pintype "passive+no_connect"))
    )
    (net (code "64") (name "unconnected-(U13-P0.3-Pad31)") (class "Default")
      (node (ref "U13") (pin "31") (pinfunction "P0.3_31") (pintype "passive+no_connect"))
    )
    (net (code "65") (name "unconnected-(U13-P0.6-Pad28)") (class "Default")
      (node (ref "U13") (pin "28") (pinfunction "P0.6_28") (pintype "passive+no_connect"))
    )
    (net (code "66") (name "unconnected-(U13-P2.5-Pad13)") (class "Default")
      (node (ref "U13") (pin "13") (pinfunction "P2.5_13") (pintype "passive+no_connect"))
    )
    (net (code "67") (name "unconnected-(U13-P2.6-Pad12)") (class "Default")
      (node (ref "U13") (pin "12") (pinfunction "P2.6_12") (pintype "passive+no_connect"))
    )
    (net (code "68") (name "unconnected-(U13-P2.7-Pad11)") (class "Default")
      (node (ref "U13") (pin "11") (pinfunction "P2.7_11") (pintype "passive+no_connect"))
    )
    (net (code "69") (name "unconnected-(U18-CTS-Pad23)") (class "Default")
      (node (ref "U18") (pin "23") (pinfunction "CTS_23") (pintype "passive+no_connect"))
    )
    (net (code "70") (name "unconnected-(U18-DCD-Pad1)") (class "Default")
      (node (ref "U18") (pin "1") (pinfunction "DCD_1") (pintype "passive+no_connect"))
    )
    (net (code "71") (name "unconnected-(U18-DSR-Pad27)") (class "Default")
      (node (ref "U18") (pin "27") (pinfunction "DSR_27") (pintype "passive+no_connect"))
    )
    (net (code "72") (name "unconnected-(U18-DTR-Pad28)") (class "Default")
      (node (ref "U18") (pin "28") (pinfunction "DTR_28") (pintype "passive+no_connect"))
    )
    (net (code "73") (name "unconnected-(U18-NC-Pad10)") (class "Default")
      (node (ref "U18") (pin "10") (pinfunction "NC_10") (pintype "passive+no_connect"))
    )
    (net (code "74") (name "unconnected-(U18-NC-Pad13)") (class "Default")
      (node (ref "U18") (pin "13") (pinfunction "NC_13") (pintype "passive+no_connect"))
    )
    (net (code "75") (name "unconnected-(U18-NC-Pad14)") (class "Default")
      (node (ref "U18") (pin "14") (pinfunction "NC_14") (pintype "passive+no_connect"))
    )
    (net (code "76") (name "unconnected-(U18-NC-Pad15)") (class "Default")
      (node (ref "U18") (pin "15") (pinfunction "NC_15") (pintype "passive+no_connect"))
    )
    (net (code "77") (name "unconnected-(U18-NC-Pad16)") (class "Default")
      (node (ref "U18") (pin "16") (pinfunction "NC_16") (pintype "passive+no_connect"))
    )
    (net (code "78") (name "unconnected-(U18-NC-Pad17)") (class "Default")
      (node (ref "U18") (pin "17") (pinfunction "NC_17") (pintype "passive+no_connect"))
    )
    (net (code "79") (name "unconnected-(U18-NC-Pad18)") (class "Default")
      (node (ref "U18") (pin "18") (pinfunction "NC_18") (pintype "passive+no_connect"))
    )
    (net (code "80") (name "unconnected-(U18-NC-Pad19)") (class "Default")
      (node (ref "U18") (pin "19") (pinfunction "NC_19") (pintype "passive+no_connect"))
    )
    (net (code "81") (name "unconnected-(U18-NC-Pad20)") (class "Default")
      (node (ref "U18") (pin "20") (pinfunction "NC_20") (pintype "passive+no_connect"))
    )
    (net (code "82") (name "unconnected-(U18-NC-Pad21)") (class "Default")
      (node (ref "U18") (pin "21") (pinfunction "NC_21") (pintype "passive+no_connect"))
    )
    (net (code "83") (name "unconnected-(U18-NC-Pad22)") (class "Default")
      (node (ref "U18") (pin "22") (pinfunction "NC_22") (pintype "passive+no_connect"))
    )
    (net (code "84") (name "unconnected-(U18-RI-Pad2)") (class "Default")
      (node (ref "U18") (pin "2") (pinfunction "RI_2") (pintype "passive+no_connect"))
    )
    (net (code "85") (name "unconnected-(U18-RTS-Pad24)") (class "Default")
      (node (ref "U18") (pin "24") (pinfunction "RTS_24") (pintype "passive+no_connect"))
    )
    (net (code "86") (name "unconnected-(U18-SUSPEND-Pad12)") (class "Default")
      (node (ref "U18") (pin "12") (pinfunction "SUSPEND_12") (pintype "passive+no_connect"))
    )
    (net (code "87") (name "unconnected-(U18-~{SUSPEND}-Pad11)") (class "Default")
      (node (ref "U18") (pin "11") (pinfunction "~{SUSPEND}_11") (pintype "passive+no_connect"))
    )
  )
)
